# GateDriver.net
KiCad netlist of a schematic drawn in Altium Designer
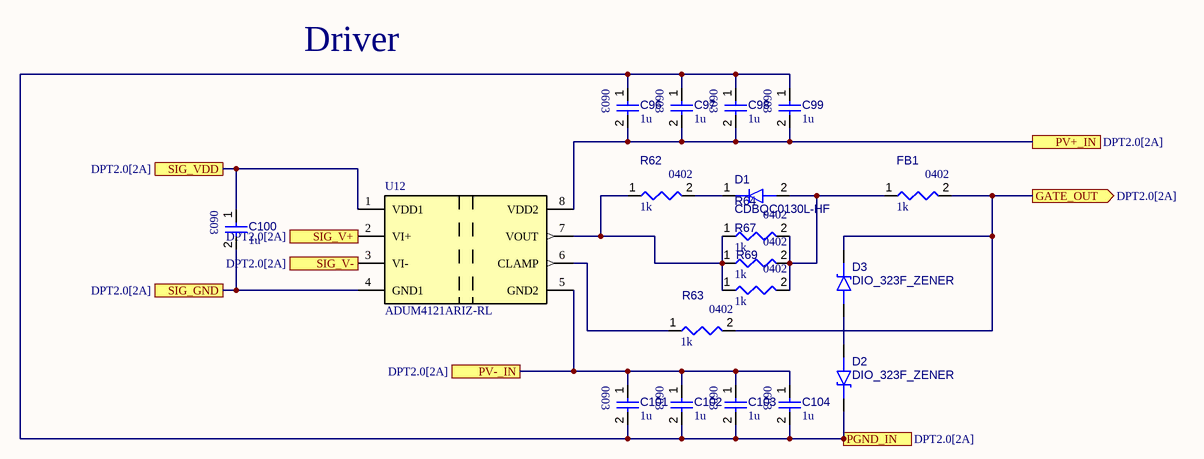
[diagram p0: GateDriver.SchDoc]

(export (version "E")
  (design (tool "Eeschema 10.0.6"))
  (components
    (comp (ref "C96")
      (value "1u")
      (footprint "CAP_0603_HIGH")
      (description "Non polarized SMD capacitor - 0603 (1608 Metric)")
      (fields (field (name "Comment") "CAP-0603"))
      (libsource (lib "2256-GaN Power") (part "CAP-NP-2"))
    )
    (comp (ref "C97")
      (value "1u")
      (footprint "CAP_0603_HIGH")
      (description "Non polarized SMD capacitor - 0603 (1608 Metric)")
      (fields (field (name "Comment") "CAP-0603"))
      (libsource (lib "2256-GaN Power") (part "CAP-NP-2"))
    )
    (comp (ref "C98")
      (value "1u")
      (footprint "CAP_0603_HIGH")
      (description "Non polarized SMD capacitor - 0603 (1608 Metric)")
      (fields (field (name "Comment") "CAP-0603"))
      (libsource (lib "2256-GaN Power") (part "CAP-NP-2"))
    )
    (comp (ref "C99")
      (value "1u")
      (footprint "CAP_0603_HIGH")
      (description "Non polarized SMD capacitor - 0603 (1608 Metric)")
      (fields (field (name "Comment") "CAP-0603"))
      (libsource (lib "2256-GaN Power") (part "CAP-NP-2"))
    )
    (comp (ref "C100")
      (value "1u")
      (footprint "CAP_0603_HIGH")
      (description "Non polarized SMD capacitor - 0603 (1608 Metric)")
      (fields (field (name "Comment") "CAP-0603"))
      (libsource (lib "2256-GaN Power") (part "CAP-NP-2"))
    )
    (comp (ref "C101")
      (value "1u")
      (footprint "CAP_0603_HIGH")
      (description "Non polarized SMD capacitor - 0603 (1608 Metric)")
      (fields (field (name "Comment") "CAP-0603"))
      (libsource (lib "2256-GaN Power") (part "CAP-NP-2"))
    )
    (comp (ref "C102")
      (value "1u")
      (footprint "CAP_0603_HIGH")
      (description "Non polarized SMD capacitor - 0603 (1608 Metric)")
      (fields (field (name "Comment") "CAP-0603"))
      (libsource (lib "2256-GaN Power") (part "CAP-NP-2"))
    )
    (comp (ref "C103")
      (value "1u")
      (footprint "CAP_0603_HIGH")
      (description "Non polarized SMD capacitor - 0603 (1608 Metric)")
      (fields (field (name "Comment") "CAP-0603"))
      (libsource (lib "2256-GaN Power") (part "CAP-NP-2"))
    )
    (comp (ref "C104")
      (value "1u")
      (footprint "CAP_0603_HIGH")
      (description "Non polarized SMD capacitor - 0603 (1608 Metric)")
      (fields (field (name "Comment") "CAP-0603"))
      (libsource (lib "2256-GaN Power") (part "CAP-NP-2"))
    )
    (comp (ref "D1")
      (value "CDBQC0130L-HF")
      (footprint "DIO_SOD-923F")
      (description "Low VF SMD Schottky Barrier Diode")
      (libsource (lib "2256-GaN Power") (part "DIODE-2"))
    )
    (comp (ref "D2")
      (value "DIO_323F_ZENER")
      (footprint "DIO_SOD-323F")
      (description "Generic SOD-323F Zener diode")
      (libsource (lib "2256-GaN Power") (part "DIODE-ZEN-2"))
    )
    (comp (ref "D3")
      (value "DIO_323F_ZENER")
      (footprint "DIO_SOD-323F")
      (description "Generic SOD-323F Zener diode")
      (libsource (lib "2256-GaN Power") (part "DIODE-ZEN-2"))
    )
    (comp (ref "FB1")
      (value "1k")
      (footprint "RES_0402_HIGH")
      (description "SMD Resistor - 0402 (1005 Metric)")
      (fields (field (name "Comment") "RES-0402"))
      (libsource (lib "2256-GaN Power") (part "RES-2"))
    )
    (comp (ref "R62")
      (value "1k")
      (footprint "RES_0402_HIGH")
      (description "SMD Resistor - 0402 (1005 Metric)")
      (fields (field (name "Comment") "RES-0402"))
      (libsource (lib "2256-GaN Power") (part "RES-2"))
    )
    (comp (ref "R63")
      (value "1k")
      (footprint "RES_0402_HIGH")
      (description "SMD Resistor - 0402 (1005 Metric)")
      (fields (field (name "Comment") "RES-0402"))
      (libsource (lib "2256-GaN Power") (part "RES-2"))
    )
    (comp (ref "R64")
      (value "1k")
      (footprint "RES_0402_HIGH")
      (description "SMD Resistor - 0402 (1005 Metric)")
      (fields (field (name "Comment") "RES-0402"))
      (libsource (lib "2256-GaN Power") (part "RES-2"))
    )
    (comp (ref "R67")
      (value "1k")
      (footprint "RES_0402_HIGH")
      (description "SMD Resistor - 0402 (1005 Metric)")
      (fields (field (name "Comment") "RES-0402"))
      (libsource (lib "2256-GaN Power") (part "RES-2"))
    )
    (comp (ref "R69")
      (value "1k")
      (footprint "RES_0402_HIGH")
      (description "SMD Resistor - 0402 (1005 Metric)")
      (fields (field (name "Comment") "RES-0402"))
      (libsource (lib "2256-GaN Power") (part "RES-2"))
    )
    (comp (ref "U12")
      (value "ADUM4121ARIZ-RL")
      (footprint "SOIC-8_WIDE")
      (description "DGTL ISO 5KV 1CH GATE DRVR 8SOIC")
      (libsource (lib "2256-GaN Power") (part "ADUM4121"))
    )
  )
  (nets
    (net (code "1") (name "/GATE_OUT") (class "Default")
      (node (ref "D3") (pin "1") (pinfunction "K_1") (pintype "passive"))
      (node (ref "FB1") (pin "2") (pinfunction "2_2") (pintype "passive"))
      (node (ref "R63") (pin "2") (pinfunction "2_2") (pintype "passive"))
    )
    (net (code "2") (name "/PGND_IN") (class "Default")
      (node (ref "C101") (pin "2") (pinfunction "2_2") (pintype "passive"))
      (node (ref "C102") (pin "2") (pinfunction "2_2") (pintype "passive"))
      (node (ref "C103") (pin "2") (pinfunction "2_2") (pintype "passive"))
      (node (ref "C104") (pin "2") (pinfunction "2_2") (pintype "passive"))
      (node (ref "C96") (pin "1") (pinfunction "1_1") (pintype "passive"))
      (node (ref "C97") (pin "1") (pinfunction "1_1") (pintype "passive"))
      (node (ref "C98") (pin "1") (pinfunction "1_1") (pintype "passive"))
      (node (ref "C99") (pin "1") (pinfunction "1_1") (pintype "passive"))
      (node (ref "D2") (pin "1") (pinfunction "K_1") (pintype "passive"))
    )
    (net (code "3") (name "/PV+_IN") (class "Default")
      (node (ref "C96") (pin "2") (pinfunction "2_2") (pintype "passive"))
      (node (ref "C97") (pin "2") (pinfunction "2_2") (pintype "passive"))
      (node (ref "C98") (pin "2") (pinfunction "2_2") (pintype "passive"))
      (node (ref "C99") (pin "2") (pinfunction "2_2") (pintype "passive"))
      (node (ref "U12") (pin "8") (pinfunction "VDD2_8") (pintype "power_in"))
    )
    (net (code "4") (name "/PV-_IN") (class "Default")
      (node (ref "C101") (pin "1") (pinfunction "1_1") (pintype "passive"))
      (node (ref "C102") (pin "1") (pinfunction "1_1") (pintype "passive"))
      (node (ref "C103") (pin "1") (pinfunction "1_1") (pintype "passive"))
      (node (ref "C104") (pin "1") (pinfunction "1_1") (pintype "passive"))
      (node (ref "U12") (pin "5") (pinfunction "GND2_5") (pintype "power_in"))
    )
    (net (code "5") (name "/SIG_GND") (class "Default")
      (node (ref "C100") (pin "2") (pinfunction "2_2") (pintype "passive"))
      (node (ref "U12") (pin "4") (pinfunction "GND1_4") (pintype "power_in"))
    )
    (net (code "6") (name "/SIG_V+") (class "Default")
      (node (ref "U12") (pin "2") (pinfunction "VI+_2") (pintype "passive"))
    )
    (net (code "7") (name "/SIG_V-") (class "Default")
      (node (ref "U12") (pin "3") (pinfunction "VI-_3") (pintype "passive"))
    )
    (net (code "8") (name "/SIG_VDD") (class "Default")
      (node (ref "C100") (pin "1") (pinfunction "1_1") (pintype "passive"))
      (node (ref "U12") (pin "1") (pinfunction "VDD1_1") (pintype "power_in"))
    )
    (net (code "9") (name "Net-(D1-A)") (class "Default")
      (node (ref "D1") (pin "2") (pinfunction "A_2") (pintype "passive"))
      (node (ref "FB1") (pin "1") (pinfunction "1_1") (pintype "passive"))
      (node (ref "R64") (pin "2") (pinfunction "2_2") (pintype "passive"))
      (node (ref "R67") (pin "2") (pinfunction "2_2") (pintype "passive"))
      (node (ref "R69") (pin "2") (pinfunction "2_2") (pintype "passive"))
    )
    (net (code "10") (name "Net-(D1-K)") (class "Default")
      (node (ref "D1") (pin "1") (pinfunction "K_1") (pintype "passive"))
      (node (ref "R62") (pin "2") (pinfunction "2_2") (pintype "passive"))
    )
    (net (code "11") (name "Net-(D2-A)") (class "Default")
      (node (ref "D2") (pin "2") (pinfunction "A_2") (pintype "passive"))
      (node (ref "D3") (pin "2") (pinfunction "A_2") (pintype "passive"))
    )
    (net (code "12") (name "Net-(U12-CLAMP)") (class "Default")
      (node (ref "R63") (pin "1") (pinfunction "1_1") (pintype "passive"))
      (node (ref "U12") (pin "6") (pinfunction "CLAMP_6") (pintype "output"))
    )
    (net (code "13") (name "Net-(U12-VOUT)") (class "Default")
      (node (ref "R62") (pin "1") (pinfunction "1_1") (pintype "passive"))
      (node (ref "R64") (pin "1") (pinfunction "1_1") (pintype "passive"))
      (node (ref "R67") (pin "1") (pinfunction "1_1") (pintype "passive"))
      (node (ref "R69") (pin "1") (pinfunction "1_1") (pintype "passive"))
      (node (ref "U12") (pin "7") (pinfunction "VOUT_7") (pintype "output"))
    )
  )
)
